# HVC-NROM.net
KiCad netlist of a schematic drawn in EAGLE
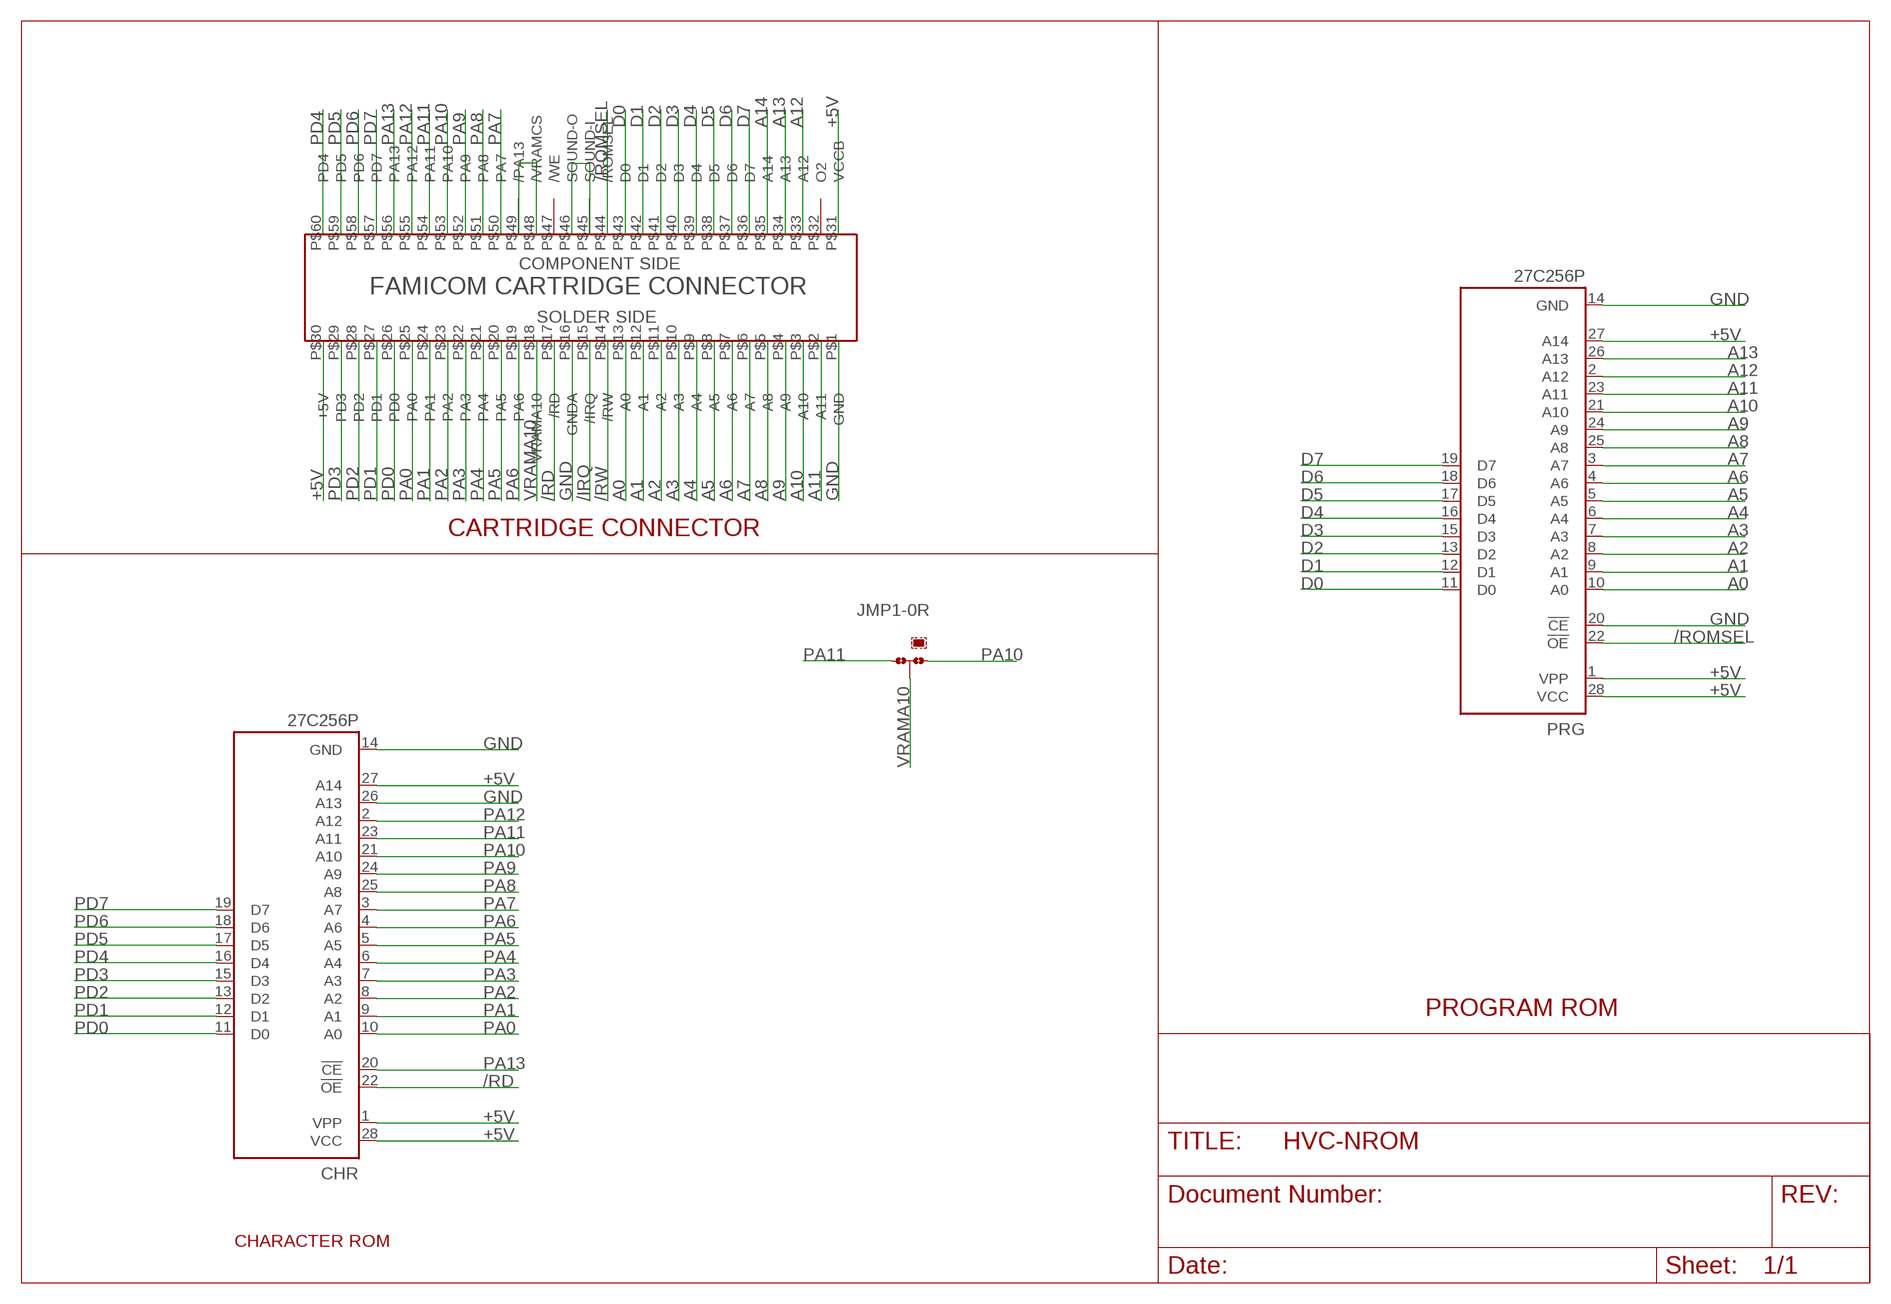
[diagram p0: schematic, sheet 1]

(export (version "E")
  (design (tool "Eeschema 10.0.6"))
  (components
    (comp (ref "CHR")
      (value "27C256P")
      (footprint "eagle-import:DIL28-6")
      (fields (field (name "MF") "Arrow Electronics") (field (name "MPN") "M27C256B15F1"))
      (libsource (lib "eagle-import") (part "27256PC"))
    )
    (comp (ref "JMP1")
      (value "0R-JUMPA")
      (footprint "eagle-import:A0R-JMP")
      (libsource (lib "eagle-import") (part "0R-JUMPA"))
    )
    (comp (ref "PRG")
      (value "27C256P")
      (footprint "eagle-import:DIL28-6")
      (fields (field (name "MF") "Arrow Electronics") (field (name "MPN") "M27C256B15F1"))
      (libsource (lib "eagle-import") (part "27256PC"))
    )
    (comp (ref "U$1")
      (value "FC-60-CART-PIN")
      (footprint "eagle-import:FC-60-PIN-CART")
      (libsource (lib "eagle-import") (part "FC-60-CART-PIN"))
    )
  )
  (nets
    (net (code "1") (name "/+5V") (class "Default")
      (node (ref "CHR") (pin "1") (pinfunction "VPP_1") (pintype "input"))
      (node (ref "CHR") (pin "27") (pinfunction "A14_27") (pintype "input"))
      (node (ref "CHR") (pin "28") (pinfunction "VCC_28") (pintype "power_in"))
      (node (ref "PRG") (pin "1") (pinfunction "VPP_1") (pintype "input"))
      (node (ref "PRG") (pin "27") (pinfunction "A14_27") (pintype "input"))
      (node (ref "PRG") (pin "28") (pinfunction "VCC_28") (pintype "power_in"))
      (node (ref "U$1") (pin "P$30") (pinfunction "+5V_P$30") (pintype "power_in"))
      (node (ref "U$1") (pin "P$31") (pinfunction "VCCB_P$31") (pintype "power_in"))
    )
    (net (code "2") (name "/A0") (class "Default")
      (node (ref "PRG") (pin "10") (pinfunction "A0_10") (pintype "input"))
      (node (ref "U$1") (pin "P$13") (pinfunction "A0_P$13") (pintype "bidirectional"))
    )
    (net (code "3") (name "/A1") (class "Default")
      (node (ref "PRG") (pin "9") (pinfunction "A1_9") (pintype "input"))
      (node (ref "U$1") (pin "P$12") (pinfunction "A1_P$12") (pintype "bidirectional"))
    )
    (net (code "4") (name "/A2") (class "Default")
      (node (ref "PRG") (pin "8") (pinfunction "A2_8") (pintype "input"))
      (node (ref "U$1") (pin "P$11") (pinfunction "A2_P$11") (pintype "bidirectional"))
    )
    (net (code "5") (name "/A3") (class "Default")
      (node (ref "PRG") (pin "7") (pinfunction "A3_7") (pintype "input"))
      (node (ref "U$1") (pin "P$10") (pinfunction "A3_P$10") (pintype "bidirectional"))
    )
    (net (code "6") (name "/A4") (class "Default")
      (node (ref "PRG") (pin "6") (pinfunction "A4_6") (pintype "input"))
      (node (ref "U$1") (pin "P$9") (pinfunction "A4_P$9") (pintype "bidirectional"))
    )
    (net (code "7") (name "/A5") (class "Default")
      (node (ref "PRG") (pin "5") (pinfunction "A5_5") (pintype "input"))
      (node (ref "U$1") (pin "P$8") (pinfunction "A5_P$8") (pintype "bidirectional"))
    )
    (net (code "8") (name "/A6") (class "Default")
      (node (ref "PRG") (pin "4") (pinfunction "A6_4") (pintype "input"))
      (node (ref "U$1") (pin "P$7") (pinfunction "A6_P$7") (pintype "bidirectional"))
    )
    (net (code "9") (name "/A7") (class "Default")
      (node (ref "PRG") (pin "3") (pinfunction "A7_3") (pintype "input"))
      (node (ref "U$1") (pin "P$6") (pinfunction "A7_P$6") (pintype "bidirectional"))
    )
    (net (code "10") (name "/A8") (class "Default")
      (node (ref "PRG") (pin "25") (pinfunction "A8_25") (pintype "input"))
      (node (ref "U$1") (pin "P$5") (pinfunction "A8_P$5") (pintype "bidirectional"))
    )
    (net (code "11") (name "/A9") (class "Default")
      (node (ref "PRG") (pin "24") (pinfunction "A9_24") (pintype "input"))
      (node (ref "U$1") (pin "P$4") (pinfunction "A9_P$4") (pintype "bidirectional"))
    )
    (net (code "12") (name "/A10") (class "Default")
      (node (ref "PRG") (pin "21") (pinfunction "A10_21") (pintype "input"))
      (node (ref "U$1") (pin "P$3") (pinfunction "A10_P$3") (pintype "bidirectional"))
    )
    (net (code "13") (name "/A11") (class "Default")
      (node (ref "PRG") (pin "23") (pinfunction "A11_23") (pintype "input"))
      (node (ref "U$1") (pin "P$2") (pinfunction "A11_P$2") (pintype "bidirectional"))
    )
    (net (code "14") (name "/A12") (class "Default")
      (node (ref "PRG") (pin "2") (pinfunction "A12_2") (pintype "input"))
      (node (ref "U$1") (pin "P$33") (pinfunction "A12_P$33") (pintype "bidirectional"))
    )
    (net (code "15") (name "/A13") (class "Default")
      (node (ref "PRG") (pin "26") (pinfunction "A13_26") (pintype "input"))
      (node (ref "U$1") (pin "P$34") (pinfunction "A13_P$34") (pintype "bidirectional"))
    )
    (net (code "16") (name "/A14") (class "Default")
      (node (ref "U$1") (pin "P$35") (pinfunction "A14_P$35") (pintype "bidirectional"))
    )
    (net (code "17") (name "/D0") (class "Default")
      (node (ref "PRG") (pin "11") (pinfunction "D0_11") (pintype "tri_state"))
      (node (ref "U$1") (pin "P$43") (pinfunction "D0_P$43") (pintype "bidirectional"))
    )
    (net (code "18") (name "/D1") (class "Default")
      (node (ref "PRG") (pin "12") (pinfunction "D1_12") (pintype "tri_state"))
      (node (ref "U$1") (pin "P$42") (pinfunction "D1_P$42") (pintype "bidirectional"))
    )
    (net (code "19") (name "/D2") (class "Default")
      (node (ref "PRG") (pin "13") (pinfunction "D2_13") (pintype "tri_state"))
      (node (ref "U$1") (pin "P$41") (pinfunction "D2_P$41") (pintype "bidirectional"))
    )
    (net (code "20") (name "/D3") (class "Default")
      (node (ref "PRG") (pin "15") (pinfunction "D3_15") (pintype "tri_state"))
      (node (ref "U$1") (pin "P$40") (pinfunction "D3_P$40") (pintype "bidirectional"))
    )
    (net (code "21") (name "/D4") (class "Default")
      (node (ref "PRG") (pin "16") (pinfunction "D4_16") (pintype "tri_state"))
      (node (ref "U$1") (pin "P$39") (pinfunction "D4_P$39") (pintype "bidirectional"))
    )
    (net (code "22") (name "/D5") (class "Default")
      (node (ref "PRG") (pin "17") (pinfunction "D5_17") (pintype "tri_state"))
      (node (ref "U$1") (pin "P$38") (pinfunction "D5_P$38") (pintype "bidirectional"))
    )
    (net (code "23") (name "/D6") (class "Default")
      (node (ref "PRG") (pin "18") (pinfunction "D6_18") (pintype "tri_state"))
      (node (ref "U$1") (pin "P$37") (pinfunction "D6_P$37") (pintype "bidirectional"))
    )
    (net (code "24") (name "/D7") (class "Default")
      (node (ref "PRG") (pin "19") (pinfunction "D7_19") (pintype "tri_state"))
      (node (ref "U$1") (pin "P$36") (pinfunction "D7_P$36") (pintype "bidirectional"))
    )
    (net (code "25") (name "/GND") (class "Default")
      (node (ref "CHR") (pin "14") (pinfunction "GND_14") (pintype "power_in"))
      (node (ref "CHR") (pin "26") (pinfunction "A13_26") (pintype "input"))
      (node (ref "PRG") (pin "14") (pinfunction "GND_14") (pintype "power_in"))
      (node (ref "PRG") (pin "20") (pinfunction "~{CE}_20") (pintype "input"))
      (node (ref "U$1") (pin "P$1") (pinfunction "GND_P$1") (pintype "power_in"))
      (node (ref "U$1") (pin "P$16") (pinfunction "GNDA_P$16") (pintype "power_in"))
    )
    (net (code "26") (name "/PA0") (class "Default")
      (node (ref "CHR") (pin "10") (pinfunction "A0_10") (pintype "input"))
      (node (ref "U$1") (pin "P$25") (pinfunction "PA0_P$25") (pintype "bidirectional"))
    )
    (net (code "27") (name "/PA1") (class "Default")
      (node (ref "CHR") (pin "9") (pinfunction "A1_9") (pintype "input"))
      (node (ref "U$1") (pin "P$24") (pinfunction "PA1_P$24") (pintype "bidirectional"))
    )
    (net (code "28") (name "/PA2") (class "Default")
      (node (ref "CHR") (pin "8") (pinfunction "A2_8") (pintype "input"))
      (node (ref "U$1") (pin "P$23") (pinfunction "PA2_P$23") (pintype "bidirectional"))
    )
    (net (code "29") (name "/PA3") (class "Default")
      (node (ref "CHR") (pin "7") (pinfunction "A3_7") (pintype "input"))
      (node (ref "U$1") (pin "P$22") (pinfunction "PA3_P$22") (pintype "bidirectional"))
    )
    (net (code "30") (name "/PA4") (class "Default")
      (node (ref "CHR") (pin "6") (pinfunction "A4_6") (pintype "input"))
      (node (ref "U$1") (pin "P$21") (pinfunction "PA4_P$21") (pintype "bidirectional"))
    )
    (net (code "31") (name "/PA5") (class "Default")
      (node (ref "CHR") (pin "5") (pinfunction "A5_5") (pintype "input"))
      (node (ref "U$1") (pin "P$20") (pinfunction "PA5_P$20") (pintype "bidirectional"))
    )
    (net (code "32") (name "/PA6") (class "Default")
      (node (ref "CHR") (pin "4") (pinfunction "A6_4") (pintype "input"))
      (node (ref "U$1") (pin "P$19") (pinfunction "PA6_P$19") (pintype "bidirectional"))
    )
    (net (code "33") (name "/PA7") (class "Default")
      (node (ref "CHR") (pin "3") (pinfunction "A7_3") (pintype "input"))
      (node (ref "U$1") (pin "P$50") (pinfunction "PA7_P$50") (pintype "bidirectional"))
    )
    (net (code "34") (name "/PA8") (class "Default")
      (node (ref "CHR") (pin "25") (pinfunction "A8_25") (pintype "input"))
      (node (ref "U$1") (pin "P$51") (pinfunction "PA8_P$51") (pintype "bidirectional"))
    )
    (net (code "35") (name "/PA9") (class "Default")
      (node (ref "CHR") (pin "24") (pinfunction "A9_24") (pintype "input"))
      (node (ref "U$1") (pin "P$52") (pinfunction "PA9_P$52") (pintype "bidirectional"))
    )
    (net (code "36") (name "/PA10") (class "Default")
      (node (ref "CHR") (pin "21") (pinfunction "A10_21") (pintype "input"))
      (node (ref "JMP1") (pin "1") (pinfunction "1_1") (pintype "passive"))
      (node (ref "U$1") (pin "P$53") (pinfunction "PA10_P$53") (pintype "bidirectional"))
    )
    (net (code "37") (name "/PA11") (class "Default")
      (node (ref "CHR") (pin "23") (pinfunction "A11_23") (pintype "input"))
      (node (ref "JMP1") (pin "3") (pinfunction "3_3") (pintype "passive"))
      (node (ref "U$1") (pin "P$54") (pinfunction "PA11_P$54") (pintype "bidirectional"))
    )
    (net (code "38") (name "/PA12") (class "Default")
      (node (ref "CHR") (pin "2") (pinfunction "A12_2") (pintype "input"))
      (node (ref "U$1") (pin "P$55") (pinfunction "PA12_P$55") (pintype "bidirectional"))
    )
    (net (code "39") (name "/PA13") (class "Default")
      (node (ref "CHR") (pin "20") (pinfunction "~{CE}_20") (pintype "input"))
      (node (ref "U$1") (pin "P$56") (pinfunction "PA13_P$56") (pintype "bidirectional"))
    )
    (net (code "40") (name "/PD0") (class "Default")
      (node (ref "CHR") (pin "11") (pinfunction "D0_11") (pintype "tri_state"))
      (node (ref "U$1") (pin "P$26") (pinfunction "PD0_P$26") (pintype "bidirectional"))
    )
    (net (code "41") (name "/PD1") (class "Default")
      (node (ref "CHR") (pin "12") (pinfunction "D1_12") (pintype "tri_state"))
      (node (ref "U$1") (pin "P$27") (pinfunction "PD1_P$27") (pintype "bidirectional"))
    )
    (net (code "42") (name "/PD2") (class "Default")
      (node (ref "CHR") (pin "13") (pinfunction "D2_13") (pintype "tri_state"))
      (node (ref "U$1") (pin "P$28") (pinfunction "PD2_P$28") (pintype "bidirectional"))
    )
    (net (code "43") (name "/PD3") (class "Default")
      (node (ref "CHR") (pin "15") (pinfunction "D3_15") (pintype "tri_state"))
      (node (ref "U$1") (pin "P$29") (pinfunction "PD3_P$29") (pintype "bidirectional"))
    )
    (net (code "44") (name "/PD4") (class "Default")
      (node (ref "CHR") (pin "16") (pinfunction "D4_16") (pintype "tri_state"))
      (node (ref "U$1") (pin "P$60") (pinfunction "PD4_P$60") (pintype "bidirectional"))
    )
    (net (code "45") (name "/PD5") (class "Default")
      (node (ref "CHR") (pin "17") (pinfunction "D5_17") (pintype "tri_state"))
      (node (ref "U$1") (pin "P$59") (pinfunction "PD5_P$59") (pintype "bidirectional"))
    )
    (net (code "46") (name "/PD6") (class "Default")
      (node (ref "CHR") (pin "18") (pinfunction "D6_18") (pintype "tri_state"))
      (node (ref "U$1") (pin "P$58") (pinfunction "PD6_P$58") (pintype "bidirectional"))
    )
    (net (code "47") (name "/PD7") (class "Default")
      (node (ref "CHR") (pin "19") (pinfunction "D7_19") (pintype "tri_state"))
      (node (ref "U$1") (pin "P$57") (pinfunction "PD7_P$57") (pintype "bidirectional"))
    )
    (net (code "48") (name "/VRAMA10") (class "Default")
      (node (ref "JMP1") (pin "2") (pinfunction "2_2") (pintype "passive"))
      (node (ref "U$1") (pin "P$18") (pinfunction "VRAMA10_P$18") (pintype "bidirectional"))
    )
    (net (code "49") (name "/{slash}IRQ") (class "Default")
      (node (ref "U$1") (pin "P$15") (pinfunction "/IRQ_P$15") (pintype "bidirectional"))
    )
    (net (code "50") (name "/{slash}RD") (class "Default")
      (node (ref "CHR") (pin "22") (pinfunction "~{OE}_22") (pintype "input"))
      (node (ref "U$1") (pin "P$17") (pinfunction "/RD_P$17") (pintype "bidirectional"))
    )
    (net (code "51") (name "/{slash}ROMSEL") (class "Default")
      (node (ref "PRG") (pin "22") (pinfunction "~{OE}_22") (pintype "input"))
      (node (ref "U$1") (pin "P$44") (pinfunction "/ROMSEL_P$44") (pintype "bidirectional"))
    )
    (net (code "52") (name "/{slash}RW") (class "Default")
      (node (ref "U$1") (pin "P$14") (pinfunction "/RW_P$14") (pintype "bidirectional"))
    )
    (net (code "53") (name "Net-(U$1-SOUND-I)") (class "Default")
      (node (ref "U$1") (pin "P$45") (pinfunction "SOUND-I_P$45") (pintype "bidirectional"))
      (node (ref "U$1") (pin "P$46") (pinfunction "SOUND-O_P$46") (pintype "bidirectional"))
    )
    (net (code "54") (name "Net-(U$1-{slash}PA13)") (class "Default")
      (node (ref "U$1") (pin "P$48") (pinfunction "/VRAMCS_P$48") (pintype "bidirectional"))
      (node (ref "U$1") (pin "P$49") (pinfunction "/PA13_P$49") (pintype "bidirectional"))
    )
    (net (code "55") (name "unconnected-(U$1-O2-PadP$32)") (class "Default")
      (node (ref "U$1") (pin "P$32") (pinfunction "O2_P$32") (pintype "bidirectional"))
    )
    (net (code "56") (name "unconnected-(U$1-{slash}WE-PadP$47)") (class "Default")
      (node (ref "U$1") (pin "P$47") (pinfunction "/WE_P$47") (pintype "bidirectional"))
    )
  )
)
